# PCB_4-20MA.net
KiCad netlist of a schematic drawn in Altium Designer
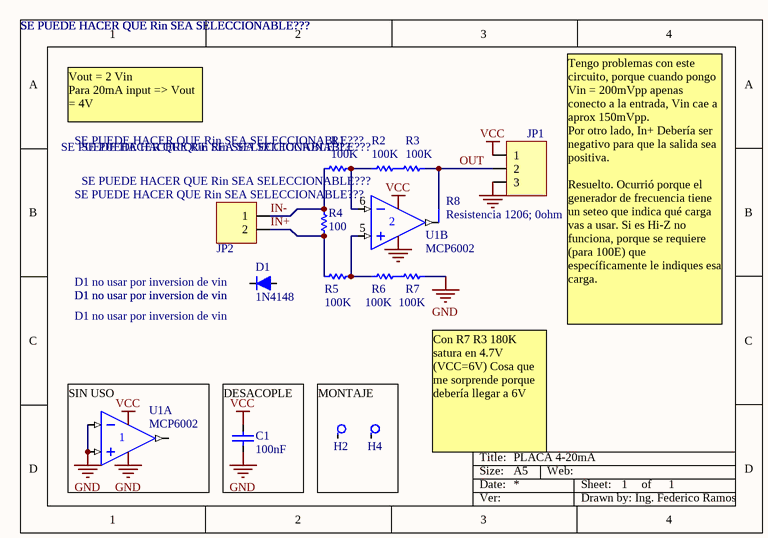
[diagram p0: PCB 4-20MA.SchDoc]

(export (version "E")
  (design (tool "Eeschema 10.0.6"))
  (components
    (comp (ref "C1")
      (value "Capacitor 1206; 100nF; 50V")
      (footprint "C1206")
      (fields (field (name "CAPACIDAD") "100nF"))
      (libsource (lib "FEDE") (part "Capacitor 1206; 100nF; 50V"))
    )
    (comp (ref "D1")
      (value "1N4148")
      (footprint "SOD123")
      (description "1N4148 SOD123")
      (libsource (lib "FEDE") (part "1N4148 SOD123"))
    )
    (comp (ref "H2")
      (value "Agujero de Montaje")
      (footprint "agujero")
      (libsource (lib "FEDE") (part "Agujero de Montaje"))
    )
    (comp (ref "H4")
      (value "Agujero de Montaje")
      (footprint "agujero")
      (libsource (lib "FEDE") (part "Agujero de Montaje"))
    )
    (comp (ref "JP1")
      (value "Header3x1")
      (footprint "conpol3x1")
      (description "Header 3x1")
      (libsource (lib "FEDE") (part "Header3x1"))
    )
    (comp (ref "JP2")
      (value "Header2x1")
      (footprint "CONPOL2X1")
      (description "Header 2x1")
      (libsource (lib "FEDE") (part "Header2x1"))
    )
    (comp (ref "R1")
      (value "Resistencia 1Kohm 5W")
      (footprint "RES300th")
      (fields (field (name "RESISTENCIA") "100K"))
      (libsource (lib "FEDE") (part "Resistencia 1Kohm 5W"))
    )
    (comp (ref "R2")
      (value "Resistencia 1Kohm 5W")
      (footprint "RES300th")
      (fields (field (name "RESISTENCIA") "100K"))
      (libsource (lib "FEDE") (part "Resistencia 1Kohm 5W"))
    )
    (comp (ref "R3")
      (value "Resistencia 1Kohm 5W")
      (footprint "RES300th")
      (fields (field (name "RESISTENCIA") "100K"))
      (libsource (lib "FEDE") (part "Resistencia 1Kohm 5W"))
    )
    (comp (ref "R4")
      (value "Resistencia 1Kohm 5W")
      (footprint "RES300th")
      (fields (field (name "RESISTENCIA") "100"))
      (libsource (lib "FEDE") (part "Resistencia 1Kohm 5W"))
    )
    (comp (ref "R5")
      (value "Resistencia 1Kohm 5W")
      (footprint "RES300th")
      (fields (field (name "RESISTENCIA") "100K"))
      (libsource (lib "FEDE") (part "Resistencia 1Kohm 5W"))
    )
    (comp (ref "R6")
      (value "Resistencia 1Kohm 5W")
      (footprint "RES300th")
      (fields (field (name "RESISTENCIA") "100K"))
      (libsource (lib "FEDE") (part "Resistencia 1Kohm 5W"))
    )
    (comp (ref "R7")
      (value "Resistencia 1Kohm 5W")
      (footprint "RES300th")
      (fields (field (name "RESISTENCIA") "100K"))
      (libsource (lib "FEDE") (part "Resistencia 1Kohm 5W"))
    )
    (comp (ref "R8")
      (value "Resistencia 1206; 0ohm")
      (footprint "R1206")
      (libsource (lib "FEDE") (part "Resistencia 1206; 0ohm"))
    )
    (comp (ref "U1")
      (value "MCP6002")
      (footprint "dip8z")
      (description "1 MHz Bandwidth Low Power Op Amp")
      (libsource (lib "FEDE") (part "MCP6002"))
    )
  )
  (nets
    (net (code "1") (name "/IN+") (class "Default")
      (node (ref "JP2") (pin "2") (pinfunction "2_2") (pintype "passive"))
      (node (ref "R4") (pin "1") (pinfunction "1_1") (pintype "passive"))
      (node (ref "R5") (pin "2") (pinfunction "2_2") (pintype "passive"))
    )
    (net (code "2") (name "/IN-") (class "Default")
      (node (ref "JP2") (pin "1") (pinfunction "1_1") (pintype "passive"))
      (node (ref "R1") (pin "2") (pinfunction "2_2") (pintype "passive"))
      (node (ref "R4") (pin "2") (pinfunction "2_2") (pintype "passive"))
    )
    (net (code "3") (name "/OUT") (class "Default")
      (node (ref "JP1") (pin "2") (pinfunction "2_2") (pintype "passive"))
      (node (ref "R3") (pin "1") (pinfunction "1_1") (pintype "passive"))
      (node (ref "R8") (pin "2") (pinfunction "2_2") (pintype "passive"))
    )
    (net (code "4") (name "GND") (class "Default")
      (node (ref "C1") (pin "1") (pinfunction "1_1") (pintype "passive"))
      (node (ref "JP1") (pin "3") (pinfunction "3_3") (pintype "passive"))
      (node (ref "R7") (pin "1") (pinfunction "1_1") (pintype "passive"))
      (node (ref "U1") (pin "2") (pinfunction "IN-_2") (pintype "input"))
      (node (ref "U1") (pin "3") (pinfunction "IN+_3") (pintype "input"))
      (node (ref "U1") (pin "4") (pinfunction "V-_4") (pintype "power_in"))
    )
    (net (code "5") (name "Net-(R2-Pad1)") (class "Default")
      (node (ref "R2") (pin "1") (pinfunction "1_1") (pintype "passive"))
      (node (ref "R3") (pin "2") (pinfunction "2_2") (pintype "passive"))
    )
    (net (code "6") (name "Net-(R6-Pad1)") (class "Default")
      (node (ref "R6") (pin "1") (pinfunction "1_1") (pintype "passive"))
      (node (ref "R7") (pin "2") (pinfunction "2_2") (pintype "passive"))
    )
    (net (code "7") (name "Net-(U1B-IN+)") (class "Default")
      (node (ref "R5") (pin "1") (pinfunction "1_1") (pintype "passive"))
      (node (ref "R6") (pin "2") (pinfunction "2_2") (pintype "passive"))
      (node (ref "U1") (pin "5") (pinfunction "IN+_5") (pintype "input"))
    )
    (net (code "8") (name "Net-(U1B-IN-)") (class "Default")
      (node (ref "R1") (pin "1") (pinfunction "1_1") (pintype "passive"))
      (node (ref "R2") (pin "2") (pinfunction "2_2") (pintype "passive"))
      (node (ref "U1") (pin "6") (pinfunction "IN-_6") (pintype "input"))
    )
    (net (code "9") (name "Net-(U1B-OUT)") (class "Default")
      (node (ref "R8") (pin "1") (pinfunction "1_1") (pintype "passive"))
      (node (ref "U1") (pin "7") (pinfunction "OUT_7") (pintype "output"))
    )
    (net (code "10") (name "VCC") (class "Default")
      (node (ref "C1") (pin "2") (pinfunction "2_2") (pintype "passive"))
      (node (ref "JP1") (pin "1") (pinfunction "1_1") (pintype "passive"))
      (node (ref "U1") (pin "8") (pinfunction "V+_8") (pintype "power_in"))
    )
    (net (code "11") (name "unconnected-(D1-Pad1)") (class "Default")
      (node (ref "D1") (pin "1") (pinfunction "1_1") (pintype "passive"))
    )
    (net (code "12") (name "unconnected-(D1-Pad2)") (class "Default")
      (node (ref "D1") (pin "2") (pinfunction "2_2") (pintype "passive"))
    )
    (net (code "13") (name "unconnected-(H2-Pad1)") (class "Default")
      (node (ref "H2") (pin "1") (pinfunction "1_1") (pintype "passive"))
    )
    (net (code "14") (name "unconnected-(H4-Pad1)") (class "Default")
      (node (ref "H4") (pin "1") (pinfunction "1_1") (pintype "passive"))
    )
    (net (code "15") (name "unconnected-(U1A-OUT-Pad1)") (class "Default")
      (node (ref "U1") (pin "1") (pinfunction "OUT_1") (pintype "output"))
    )
  )
)
